# dream_breakout.net
KiCad netlist of a schematic drawn in EAGLE
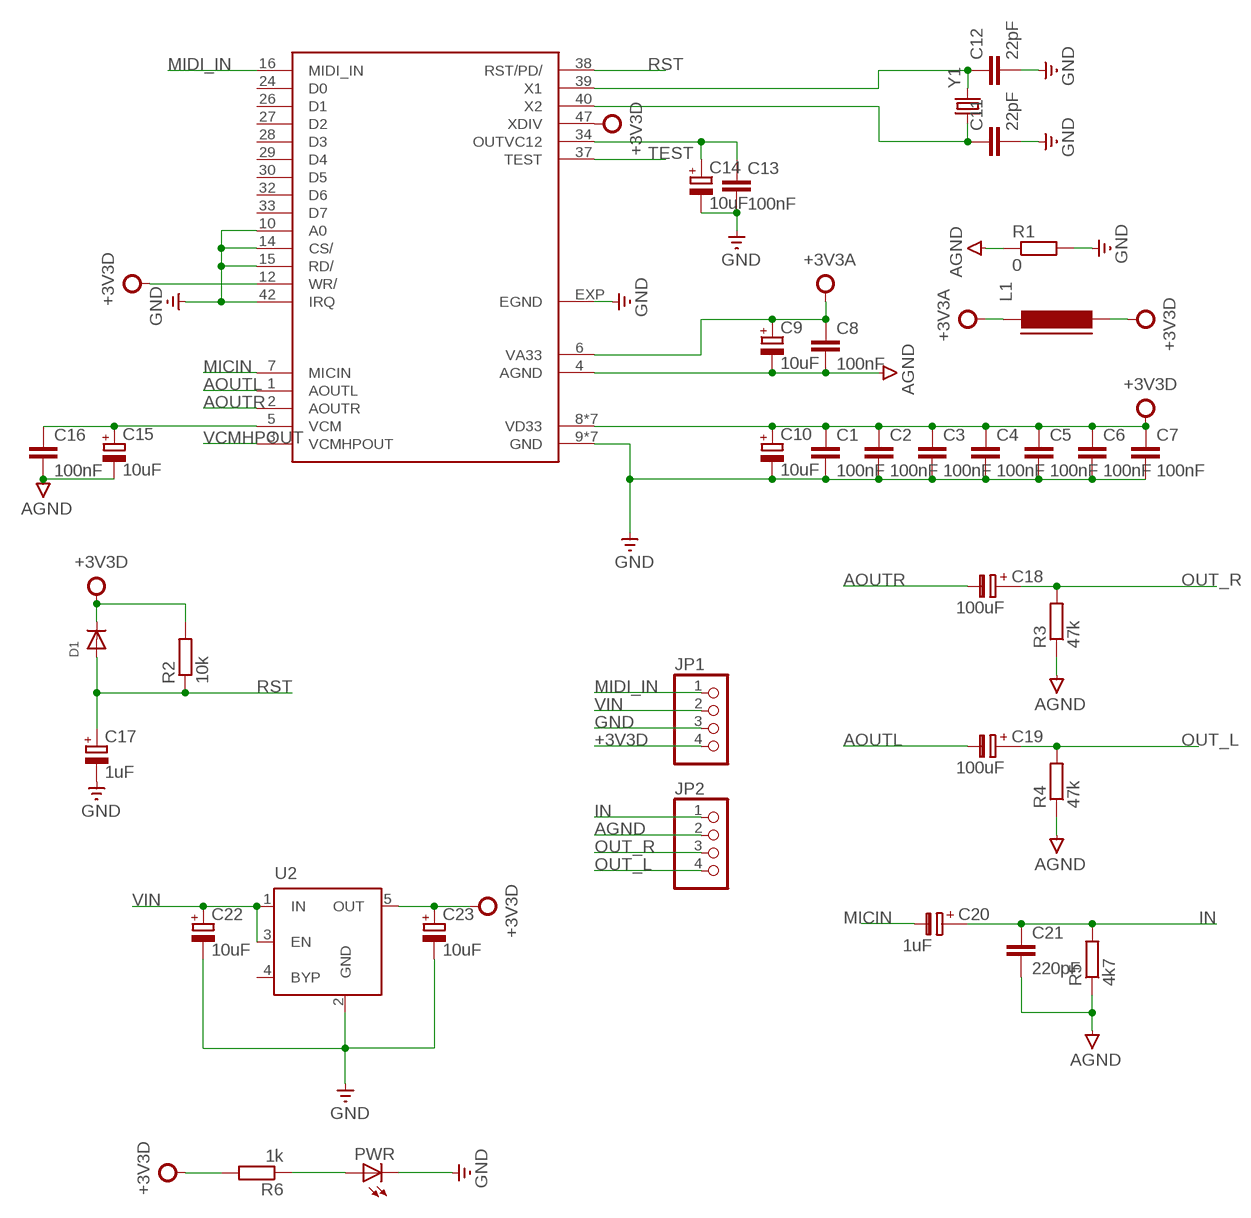
[diagram p0: schematic, sheet 1]

(export (version "E")
  (design (tool "Eeschema 10.0.6"))
  (components
    (comp (ref "C1")
      (value "100nF")
      (footprint "eagle-import:C0603K")
      (libsource (lib "eagle-import") (part "C-EUC0603K"))
    )
    (comp (ref "C2")
      (value "100nF")
      (footprint "eagle-import:C0603K")
      (libsource (lib "eagle-import") (part "C-EUC0603K"))
    )
    (comp (ref "C3")
      (value "100nF")
      (footprint "eagle-import:C0603K")
      (libsource (lib "eagle-import") (part "C-EUC0603K"))
    )
    (comp (ref "C4")
      (value "100nF")
      (footprint "eagle-import:C0603K")
      (libsource (lib "eagle-import") (part "C-EUC0603K"))
    )
    (comp (ref "C5")
      (value "100nF")
      (footprint "eagle-import:C0603K")
      (libsource (lib "eagle-import") (part "C-EUC0603K"))
    )
    (comp (ref "C6")
      (value "100nF")
      (footprint "eagle-import:C0603K")
      (libsource (lib "eagle-import") (part "C-EUC0603K"))
    )
    (comp (ref "C7")
      (value "100nF")
      (footprint "eagle-import:C0603K")
      (libsource (lib "eagle-import") (part "C-EUC0603K"))
    )
    (comp (ref "C8")
      (value "100nF")
      (footprint "eagle-import:C0603K")
      (libsource (lib "eagle-import") (part "C-EUC0603K"))
    )
    (comp (ref "C9")
      (value "10uF")
      (footprint "eagle-import:A_3216-18R")
      (libsource (lib "eagle-import") (part "CPOL-EUA/3216-18R"))
    )
    (comp (ref "C10")
      (value "10uF")
      (footprint "eagle-import:A_3216-18R")
      (libsource (lib "eagle-import") (part "CPOL-EUA/3216-18R"))
    )
    (comp (ref "C11")
      (value "22pF")
      (footprint "eagle-import:C0603K")
      (libsource (lib "eagle-import") (part "C-EUC0603K"))
    )
    (comp (ref "C12")
      (value "22pF")
      (footprint "eagle-import:C0603K")
      (libsource (lib "eagle-import") (part "C-EUC0603K"))
    )
    (comp (ref "C13")
      (value "100nF")
      (footprint "eagle-import:C0603K")
      (libsource (lib "eagle-import") (part "C-EUC0603K"))
    )
    (comp (ref "C14")
      (value "10uF")
      (footprint "eagle-import:A_3216-18R")
      (libsource (lib "eagle-import") (part "CPOL-EUA/3216-18R"))
    )
    (comp (ref "C15")
      (value "10uF")
      (footprint "eagle-import:A_3216-18R")
      (libsource (lib "eagle-import") (part "CPOL-EUA/3216-18R"))
    )
    (comp (ref "C16")
      (value "100nF")
      (footprint "eagle-import:C0603K")
      (libsource (lib "eagle-import") (part "C-EUC0603K"))
    )
    (comp (ref "C17")
      (value "1uF")
      (footprint "eagle-import:A_3216-18R")
      (libsource (lib "eagle-import") (part "CPOL-EUA/3216-18R"))
    )
    (comp (ref "C18")
      (value "100uF")
      (footprint "eagle-import:SV-B")
      (libsource (lib "eagle-import") (part "C-PR-SMD-SV-B"))
    )
    (comp (ref "C19")
      (value "100uF")
      (footprint "eagle-import:SV-B")
      (libsource (lib "eagle-import") (part "C-PR-SMD-SV-B"))
    )
    (comp (ref "C20")
      (value "1uF")
      (footprint "eagle-import:SV-B")
      (libsource (lib "eagle-import") (part "C-PR-SMD-SV-B"))
    )
    (comp (ref "C21")
      (value "220pF")
      (footprint "eagle-import:C0603K")
      (libsource (lib "eagle-import") (part "C-EUC0603K"))
    )
    (comp (ref "C22")
      (value "10uF")
      (footprint "eagle-import:A_3216-18R")
      (libsource (lib "eagle-import") (part "CPOL-EUA/3216-18R"))
    )
    (comp (ref "C23")
      (value "10uF")
      (footprint "eagle-import:A_3216-18R")
      (libsource (lib "eagle-import") (part "CPOL-EUA/3216-18R"))
    )
    (comp (ref "D1")
      (value "DIODESOD-123")
      (footprint "eagle-import:SOD-123")
      (libsource (lib "eagle-import") (part "DIODESOD-123"))
    )
    (comp (ref "JP1")
      (value "HEADER-1X4ROUND")
      (footprint "eagle-import:1X04_ROUND")
      (libsource (lib "eagle-import") (part "HEADER-1X4ROUND"))
    )
    (comp (ref "JP2")
      (value "HEADER-1X4ROUND")
      (footprint "eagle-import:1X04_ROUND")
      (libsource (lib "eagle-import") (part "HEADER-1X4ROUND"))
    )
    (comp (ref "L1")
      (value "FERRITE-0603")
      (footprint "eagle-import:FB603")
      (libsource (lib "eagle-import") (part "FERRITE-0603"))
    )
    (comp (ref "PWR")
      (value "LEDCHIP-LED0603")
      (footprint "eagle-import:CHIP-LED0603")
      (libsource (lib "eagle-import") (part "LEDCHIP-LED0603"))
    )
    (comp (ref "R1")
      (value "0")
      (footprint "eagle-import:R0603")
      (libsource (lib "eagle-import") (part "R-EU_R0603"))
    )
    (comp (ref "R2")
      (value "10k")
      (footprint "eagle-import:R0603")
      (libsource (lib "eagle-import") (part "R-EU_R0603"))
    )
    (comp (ref "R3")
      (value "47k")
      (footprint "eagle-import:R0603")
      (libsource (lib "eagle-import") (part "R-EU_R0603"))
    )
    (comp (ref "R4")
      (value "47k")
      (footprint "eagle-import:R0603")
      (libsource (lib "eagle-import") (part "R-EU_R0603"))
    )
    (comp (ref "R5")
      (value "4k7")
      (footprint "eagle-import:R0603")
      (libsource (lib "eagle-import") (part "R-EU_R0603"))
    )
    (comp (ref "R6")
      (value "1k")
      (footprint "eagle-import:R0603")
      (libsource (lib "eagle-import") (part "R-EU_R0603"))
    )
    (comp (ref "U1")
      (value "SAM2695")
      (footprint "eagle-import:QFN48")
      (libsource (lib "eagle-import") (part "SAM2695"))
    )
    (comp (ref "U2")
      (value "MIC5219XX")
      (footprint "eagle-import:SOT23-5")
      (libsource (lib "eagle-import") (part "MIC5219XX"))
    )
    (comp (ref "Y1")
      (value "CRYSTALTXC-7A")
      (footprint "eagle-import:CRYSTAL-TXC-7A")
      (libsource (lib "eagle-import") (part "CRYSTALTXC-7A"))
    )
  )
  (nets
    (net (code "1") (name "+3V3A") (class "Default")
      (node (ref "C8") (pin "1") (pinfunction "1_1") (pintype "passive"))
      (node (ref "C9") (pin "+") (pinfunction "+_+") (pintype "passive"))
      (node (ref "L1") (pin "1") (pinfunction "1_1") (pintype "passive"))
      (node (ref "U1") (pin "6") (pinfunction "VA33_6") (pintype "power_in"))
    )
    (net (code "2") (name "+3V3D") (class "Default")
      (node (ref "C1") (pin "1") (pinfunction "1_1") (pintype "passive"))
      (node (ref "C10") (pin "+") (pinfunction "+_+") (pintype "passive"))
      (node (ref "C2") (pin "1") (pinfunction "1_1") (pintype "passive"))
      (node (ref "C23") (pin "+") (pinfunction "+_+") (pintype "passive"))
      (node (ref "C3") (pin "1") (pinfunction "1_1") (pintype "passive"))
      (node (ref "C4") (pin "1") (pinfunction "1_1") (pintype "passive"))
      (node (ref "C5") (pin "1") (pinfunction "1_1") (pintype "passive"))
      (node (ref "C6") (pin "1") (pinfunction "1_1") (pintype "passive"))
      (node (ref "C7") (pin "1") (pinfunction "1_1") (pintype "passive"))
      (node (ref "D1") (pin "C") (pinfunction "C_C") (pintype "passive"))
      (node (ref "JP1") (pin "4") (pinfunction "4_4") (pintype "passive"))
      (node (ref "L1") (pin "2") (pinfunction "2_2") (pintype "passive"))
      (node (ref "R2") (pin "2") (pinfunction "2_2") (pintype "passive"))
      (node (ref "R6") (pin "2") (pinfunction "2_2") (pintype "passive"))
      (node (ref "U1") (pin "11") (pinfunction "VD33_11") (pintype "power_in"))
      (node (ref "U1") (pin "12") (pinfunction "WR/_12") (pintype "input"))
      (node (ref "U1") (pin "20") (pinfunction "VD33_20") (pintype "power_in"))
      (node (ref "U1") (pin "31") (pinfunction "VD33_31") (pintype "power_in"))
      (node (ref "U1") (pin "35") (pinfunction "VD33_35") (pintype "power_in"))
      (node (ref "U1") (pin "41") (pinfunction "VD33_41") (pintype "power_in"))
      (node (ref "U1") (pin "46") (pinfunction "VD33_46") (pintype "power_in"))
      (node (ref "U1") (pin "47") (pinfunction "XDIV_47") (pintype "input"))
      (node (ref "U1") (pin "8") (pinfunction "VD33_8") (pintype "power_in"))
      (node (ref "U2") (pin "5") (pinfunction "OUT_5") (pintype "output"))
    )
    (net (code "3") (name "/AOUTL") (class "Default")
      (node (ref "C19") (pin "-") (pinfunction "-_-") (pintype "passive"))
      (node (ref "U1") (pin "1") (pinfunction "AOUTL_1") (pintype "output"))
    )
    (net (code "4") (name "/AOUTR") (class "Default")
      (node (ref "C18") (pin "-") (pinfunction "-_-") (pintype "passive"))
      (node (ref "U1") (pin "2") (pinfunction "AOUTR_2") (pintype "output"))
    )
    (net (code "5") (name "/IN") (class "Default")
      (node (ref "C20") (pin "+") (pinfunction "+_+") (pintype "passive"))
      (node (ref "C21") (pin "1") (pinfunction "1_1") (pintype "passive"))
      (node (ref "JP2") (pin "1") (pinfunction "1_1") (pintype "passive"))
      (node (ref "R5") (pin "2") (pinfunction "2_2") (pintype "passive"))
    )
    (net (code "6") (name "/MICIN") (class "Default")
      (node (ref "C20") (pin "-") (pinfunction "-_-") (pintype "passive"))
      (node (ref "U1") (pin "7") (pinfunction "MICIN_7") (pintype "input"))
    )
    (net (code "7") (name "/MIDI_IN") (class "Default")
      (node (ref "JP1") (pin "1") (pinfunction "1_1") (pintype "passive"))
      (node (ref "U1") (pin "16") (pinfunction "MIDI_IN_16") (pintype "input"))
    )
    (net (code "8") (name "/OUT_L") (class "Default")
      (node (ref "C19") (pin "+") (pinfunction "+_+") (pintype "passive"))
      (node (ref "JP2") (pin "4") (pinfunction "4_4") (pintype "passive"))
      (node (ref "R4") (pin "2") (pinfunction "2_2") (pintype "passive"))
    )
    (net (code "9") (name "/OUT_R") (class "Default")
      (node (ref "C18") (pin "+") (pinfunction "+_+") (pintype "passive"))
      (node (ref "JP2") (pin "3") (pinfunction "3_3") (pintype "passive"))
      (node (ref "R3") (pin "2") (pinfunction "2_2") (pintype "passive"))
    )
    (net (code "10") (name "/RST") (class "Default")
      (node (ref "C17") (pin "+") (pinfunction "+_+") (pintype "passive"))
      (node (ref "D1") (pin "A") (pinfunction "A_A") (pintype "passive"))
      (node (ref "R2") (pin "1") (pinfunction "1_1") (pintype "passive"))
      (node (ref "U1") (pin "38") (pinfunction "RST/PD/_38") (pintype "input"))
    )
    (net (code "11") (name "/TEST") (class "Default")
      (node (ref "U1") (pin "37") (pinfunction "TEST_37") (pintype "input"))
    )
    (net (code "12") (name "/VCMHPOUT") (class "Default")
      (node (ref "U1") (pin "3") (pinfunction "VCMHPOUT_3") (pintype "output"))
    )
    (net (code "13") (name "/VIN") (class "Default")
      (node (ref "C22") (pin "+") (pinfunction "+_+") (pintype "passive"))
      (node (ref "JP1") (pin "2") (pinfunction "2_2") (pintype "passive"))
      (node (ref "U2") (pin "1") (pinfunction "IN_1") (pintype "input"))
      (node (ref "U2") (pin "3") (pinfunction "EN_3") (pintype "input"))
    )
    (net (code "14") (name "AGND") (class "Default")
      (node (ref "C15") (pin "-") (pinfunction "-_-") (pintype "passive"))
      (node (ref "C16") (pin "2") (pinfunction "2_2") (pintype "passive"))
      (node (ref "C21") (pin "2") (pinfunction "2_2") (pintype "passive"))
      (node (ref "C8") (pin "2") (pinfunction "2_2") (pintype "passive"))
      (node (ref "C9") (pin "-") (pinfunction "-_-") (pintype "passive"))
      (node (ref "JP2") (pin "2") (pinfunction "2_2") (pintype "passive"))
      (node (ref "R1") (pin "1") (pinfunction "1_1") (pintype "passive"))
      (node (ref "R3") (pin "1") (pinfunction "1_1") (pintype "passive"))
      (node (ref "R4") (pin "1") (pinfunction "1_1") (pintype "passive"))
      (node (ref "R5") (pin "1") (pinfunction "1_1") (pintype "passive"))
      (node (ref "U1") (pin "4") (pinfunction "AGND_4") (pintype "power_in"))
    )
    (net (code "15") (name "GND") (class "Default")
      (node (ref "C1") (pin "2") (pinfunction "2_2") (pintype "passive"))
      (node (ref "C10") (pin "-") (pinfunction "-_-") (pintype "passive"))
      (node (ref "C11") (pin "2") (pinfunction "2_2") (pintype "passive"))
      (node (ref "C12") (pin "2") (pinfunction "2_2") (pintype "passive"))
      (node (ref "C13") (pin "2") (pinfunction "2_2") (pintype "passive"))
      (node (ref "C14") (pin "-") (pinfunction "-_-") (pintype "passive"))
      (node (ref "C17") (pin "-") (pinfunction "-_-") (pintype "passive"))
      (node (ref "C2") (pin "2") (pinfunction "2_2") (pintype "passive"))
      (node (ref "C22") (pin "-") (pinfunction "-_-") (pintype "passive"))
      (node (ref "C23") (pin "-") (pinfunction "-_-") (pintype "passive"))
      (node (ref "C3") (pin "2") (pinfunction "2_2") (pintype "passive"))
      (node (ref "C4") (pin "2") (pinfunction "2_2") (pintype "passive"))
      (node (ref "C5") (pin "2") (pinfunction "2_2") (pintype "passive"))
      (node (ref "C6") (pin "2") (pinfunction "2_2") (pintype "passive"))
      (node (ref "C7") (pin "2") (pinfunction "2_2") (pintype "passive"))
      (node (ref "JP1") (pin "3") (pinfunction "3_3") (pintype "passive"))
      (node (ref "PWR") (pin "C") (pinfunction "C_C") (pintype "passive"))
      (node (ref "R1") (pin "2") (pinfunction "2_2") (pintype "passive"))
      (node (ref "U1") (pin "10") (pinfunction "A0_10") (pintype "input"))
      (node (ref "U1") (pin "13") (pinfunction "GND_13") (pintype "power_in"))
      (node (ref "U1") (pin "14") (pinfunction "CS/_14") (pintype "input"))
      (node (ref "U1") (pin "15") (pinfunction "RD/_15") (pintype "input"))
      (node (ref "U1") (pin "18") (pinfunction "GND_18") (pintype "power_in"))
      (node (ref "U1") (pin "25") (pinfunction "GND_25") (pintype "power_in"))
      (node (ref "U1") (pin "36") (pinfunction "GND_36") (pintype "power_in"))
      (node (ref "U1") (pin "42") (pinfunction "IRQ_42") (pintype "output"))
      (node (ref "U1") (pin "45") (pinfunction "GND_45") (pintype "power_in"))
      (node (ref "U1") (pin "48") (pinfunction "GND_48") (pintype "power_in"))
      (node (ref "U1") (pin "9") (pinfunction "GND_9") (pintype "power_in"))
      (node (ref "U1") (pin "EXP") (pinfunction "EGND_EXP") (pintype "power_in"))
      (node (ref "U2") (pin "2") (pinfunction "GND_2") (pintype "power_in"))
    )
    (net (code "16") (name "Net-(PWR-PadA)") (class "Default")
      (node (ref "PWR") (pin "A") (pinfunction "A_A") (pintype "passive"))
      (node (ref "R6") (pin "1") (pinfunction "1_1") (pintype "passive"))
    )
    (net (code "17") (name "Net-(U1-OUTVC12)") (class "Default")
      (node (ref "C13") (pin "1") (pinfunction "1_1") (pintype "passive"))
      (node (ref "C14") (pin "+") (pinfunction "+_+") (pintype "passive"))
      (node (ref "U1") (pin "34") (pinfunction "OUTVC12_34") (pintype "power_in"))
    )
    (net (code "18") (name "Net-(U1-VCM)") (class "Default")
      (node (ref "C15") (pin "+") (pinfunction "+_+") (pintype "passive"))
      (node (ref "C16") (pin "1") (pinfunction "1_1") (pintype "passive"))
      (node (ref "U1") (pin "5") (pinfunction "VCM_5") (pintype "output"))
    )
    (net (code "19") (name "Net-(U1-X1)") (class "Default")
      (node (ref "C12") (pin "1") (pinfunction "1_1") (pintype "passive"))
      (node (ref "U1") (pin "39") (pinfunction "X1_39") (pintype "bidirectional"))
      (node (ref "Y1") (pin "P$2") (pinfunction "2_P$2") (pintype "passive"))
    )
    (net (code "20") (name "Net-(U1-X2)") (class "Default")
      (node (ref "C11") (pin "1") (pinfunction "1_1") (pintype "passive"))
      (node (ref "U1") (pin "40") (pinfunction "X2_40") (pintype "bidirectional"))
      (node (ref "Y1") (pin "P$1") (pinfunction "1_P$1") (pintype "passive"))
    )
    (net (code "21") (name "unconnected-(U1-D0-Pad24)") (class "Default")
      (node (ref "U1") (pin "24") (pinfunction "D0_24") (pintype "bidirectional"))
    )
    (net (code "22") (name "unconnected-(U1-D1-Pad26)") (class "Default")
      (node (ref "U1") (pin "26") (pinfunction "D1_26") (pintype "bidirectional"))
    )
    (net (code "23") (name "unconnected-(U1-D2-Pad27)") (class "Default")
      (node (ref "U1") (pin "27") (pinfunction "D2_27") (pintype "bidirectional"))
    )
    (net (code "24") (name "unconnected-(U1-D3-Pad28)") (class "Default")
      (node (ref "U1") (pin "28") (pinfunction "D3_28") (pintype "bidirectional"))
    )
    (net (code "25") (name "unconnected-(U1-D4-Pad29)") (class "Default")
      (node (ref "U1") (pin "29") (pinfunction "D4_29") (pintype "bidirectional"))
    )
    (net (code "26") (name "unconnected-(U1-D5-Pad30)") (class "Default")
      (node (ref "U1") (pin "30") (pinfunction "D5_30") (pintype "bidirectional"))
    )
    (net (code "27") (name "unconnected-(U1-D6-Pad32)") (class "Default")
      (node (ref "U1") (pin "32") (pinfunction "D6_32") (pintype "bidirectional"))
    )
    (net (code "28") (name "unconnected-(U1-D7-Pad33)") (class "Default")
      (node (ref "U1") (pin "33") (pinfunction "D7_33") (pintype "bidirectional"))
    )
    (net (code "29") (name "unconnected-(U2-BYP-Pad4)") (class "Default")
      (node (ref "U2") (pin "4") (pinfunction "BYP_4") (pintype "passive"))
    )
  )
)
